# TCS230.net
KiCad netlist of a schematic drawn in Altium Designer
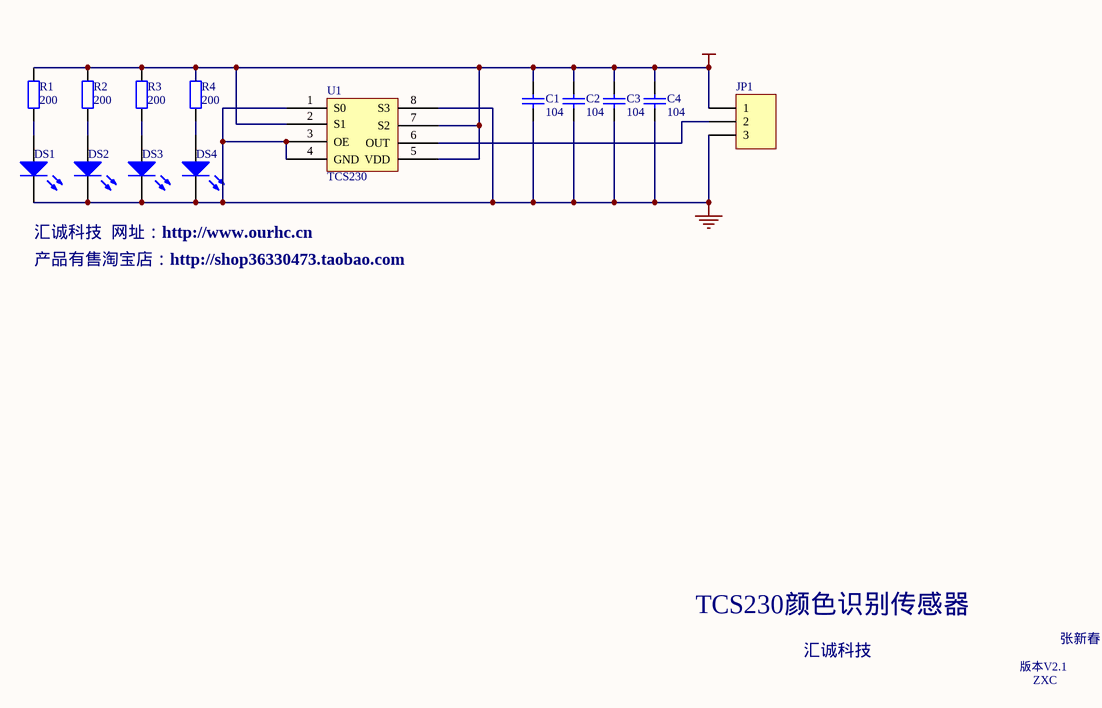
[diagram p0: TCS230颜色识别.SchDoc]

(export (version "E")
  (design (tool "Eeschema 10.0.6"))
  (components
    (comp (ref "C1")
      (value "104")
      (footprint "TP-0805-R")
      (description "瓷片电容")
      (fields (field (name "PUBLISHER") "Altium Limited"))
      (libsource (lib "zxcourhc") (part "CPDR"))
    )
    (comp (ref "C2")
      (value "104")
      (footprint "TP-0805-R")
      (description "瓷片电容")
      (fields (field (name "PUBLISHER") "Altium Limited"))
      (libsource (lib "zxcourhc") (part "CPDR"))
    )
    (comp (ref "C3")
      (value "104")
      (footprint "TP-0805-R")
      (description "瓷片电容")
      (fields (field (name "PUBLISHER") "Altium Limited"))
      (libsource (lib "zxcourhc") (part "CPDR"))
    )
    (comp (ref "C4")
      (value "104")
      (footprint "TP-0805-R")
      (description "瓷片电容")
      (fields (field (name "PUBLISHER") "Altium Limited"))
      (libsource (lib "zxcourhc") (part "CPDR"))
    )
    (comp (ref "DS1")
      (value "LED1")
      (footprint "LED_5")
      (description "Typical RED GaAs LED")
      (fields (field (name "PUBLISHER") "Altium Limited"))
      (libsource (lib "Miscellaneous Devices") (part "LED1"))
    )
    (comp (ref "DS2")
      (value "LED1")
      (footprint "LED_5")
      (description "Typical RED GaAs LED")
      (fields (field (name "PUBLISHER") "Altium Limited"))
      (libsource (lib "Miscellaneous Devices") (part "LED1"))
    )
    (comp (ref "DS3")
      (value "LED1")
      (footprint "LED_5")
      (description "Typical RED GaAs LED")
      (fields (field (name "PUBLISHER") "Altium Limited"))
      (libsource (lib "Miscellaneous Devices") (part "LED1"))
    )
    (comp (ref "DS4")
      (value "LED1")
      (footprint "LED_5")
      (description "Typical RED GaAs LED")
      (fields (field (name "PUBLISHER") "Altium Limited"))
      (libsource (lib "Miscellaneous Devices") (part "LED1"))
    )
    (comp (ref "JP1")
      (value "PZ_3")
      (footprint "HDR-3")
      (description "排针——3")
      (fields (field (name "PUBLISHER") "Altium Limited"))
      (libsource (lib "zxcourhc") (part "PZ_3"))
    )
    (comp (ref "R1")
      (value "200")
      (footprint "TP-0805-R")
      (description "Resistor")
      (fields (field (name "Comment") "Res2") (field (name "PUBLISHER") "Altium Limited"))
      (libsource (lib "Miscellaneous Devices") (part "Res2"))
    )
    (comp (ref "R2")
      (value "200")
      (footprint "TP-0805-R")
      (description "Resistor")
      (fields (field (name "Comment") "Res2") (field (name "PUBLISHER") "Altium Limited"))
      (libsource (lib "Miscellaneous Devices") (part "Res2"))
    )
    (comp (ref "R3")
      (value "200")
      (footprint "TP-0805-R")
      (description "Resistor")
      (fields (field (name "Comment") "Res2") (field (name "PUBLISHER") "Altium Limited"))
      (libsource (lib "Miscellaneous Devices") (part "Res2"))
    )
    (comp (ref "R4")
      (value "200")
      (footprint "TP-0805-R")
      (description "Resistor")
      (fields (field (name "Comment") "Res2") (field (name "PUBLISHER") "Altium Limited"))
      (libsource (lib "Miscellaneous Devices") (part "Res2"))
    )
    (comp (ref "U1")
      (value "TCS230")
      (footprint "CDFP-8")
      (description "颜色识别传感器")
      (libsource (lib "zxcourhc") (part "TCS230"))
    )
  )
  (nets
    (net (code "1") (name "GND") (class "Default")
      (node (ref "C1") (pin "1") (pinfunction "1_1") (pintype "passive"))
      (node (ref "C2") (pin "1") (pinfunction "1_1") (pintype "passive"))
      (node (ref "C3") (pin "1") (pinfunction "1_1") (pintype "passive"))
      (node (ref "C4") (pin "1") (pinfunction "1_1") (pintype "passive"))
      (node (ref "DS1") (pin "2") (pinfunction "K_2") (pintype "passive"))
      (node (ref "DS2") (pin "2") (pinfunction "K_2") (pintype "passive"))
      (node (ref "DS3") (pin "2") (pinfunction "K_2") (pintype "passive"))
      (node (ref "DS4") (pin "2") (pinfunction "K_2") (pintype "passive"))
      (node (ref "JP1") (pin "3") (pinfunction "3_3") (pintype "passive"))
      (node (ref "U1") (pin "1") (pinfunction "S0_1") (pintype "passive"))
      (node (ref "U1") (pin "3") (pinfunction "OE_3") (pintype "open_emitter"))
      (node (ref "U1") (pin "4") (pinfunction "GND_4") (pintype "passive"))
      (node (ref "U1") (pin "8") (pinfunction "S3_8") (pintype "passive"))
    )
    (net (code "2") (name "Net-(DS1-A)") (class "Default")
      (node (ref "DS1") (pin "1") (pinfunction "A_1") (pintype "passive"))
      (node (ref "R1") (pin "1") (pinfunction "1_1") (pintype "passive"))
    )
    (net (code "3") (name "Net-(DS2-A)") (class "Default")
      (node (ref "DS2") (pin "1") (pinfunction "A_1") (pintype "passive"))
      (node (ref "R2") (pin "1") (pinfunction "1_1") (pintype "passive"))
    )
    (net (code "4") (name "Net-(DS3-A)") (class "Default")
      (node (ref "DS3") (pin "1") (pinfunction "A_1") (pintype "passive"))
      (node (ref "R3") (pin "1") (pinfunction "1_1") (pintype "passive"))
    )
    (net (code "5") (name "Net-(DS4-A)") (class "Default")
      (node (ref "DS4") (pin "1") (pinfunction "A_1") (pintype "passive"))
      (node (ref "R4") (pin "1") (pinfunction "1_1") (pintype "passive"))
    )
    (net (code "6") (name "Net-(U1-OUT)") (class "Default")
      (node (ref "JP1") (pin "2") (pinfunction "2_2") (pintype "passive"))
      (node (ref "U1") (pin "6") (pinfunction "OUT_6") (pintype "passive"))
    )
    (net (code "7") (name "VCC") (class "Default")
      (node (ref "C1") (pin "2") (pinfunction "2_2") (pintype "passive"))
      (node (ref "C2") (pin "2") (pinfunction "2_2") (pintype "passive"))
      (node (ref "C3") (pin "2") (pinfunction "2_2") (pintype "passive"))
      (node (ref "C4") (pin "2") (pinfunction "2_2") (pintype "passive"))
      (node (ref "JP1") (pin "1") (pinfunction "1_1") (pintype "passive"))
      (node (ref "R1") (pin "2") (pinfunction "2_2") (pintype "passive"))
      (node (ref "R2") (pin "2") (pinfunction "2_2") (pintype "passive"))
      (node (ref "R3") (pin "2") (pinfunction "2_2") (pintype "passive"))
      (node (ref "R4") (pin "2") (pinfunction "2_2") (pintype "passive"))
      (node (ref "U1") (pin "2") (pinfunction "S1_2") (pintype "passive"))
      (node (ref "U1") (pin "5") (pinfunction "VDD_5") (pintype "passive"))
      (node (ref "U1") (pin "7") (pinfunction "S2_7") (pintype "passive"))
    )
  )
)
